# Sheet_1_2020-07-29_17-58-41.net
KiCad netlist of a schematic drawn in Altium Designer
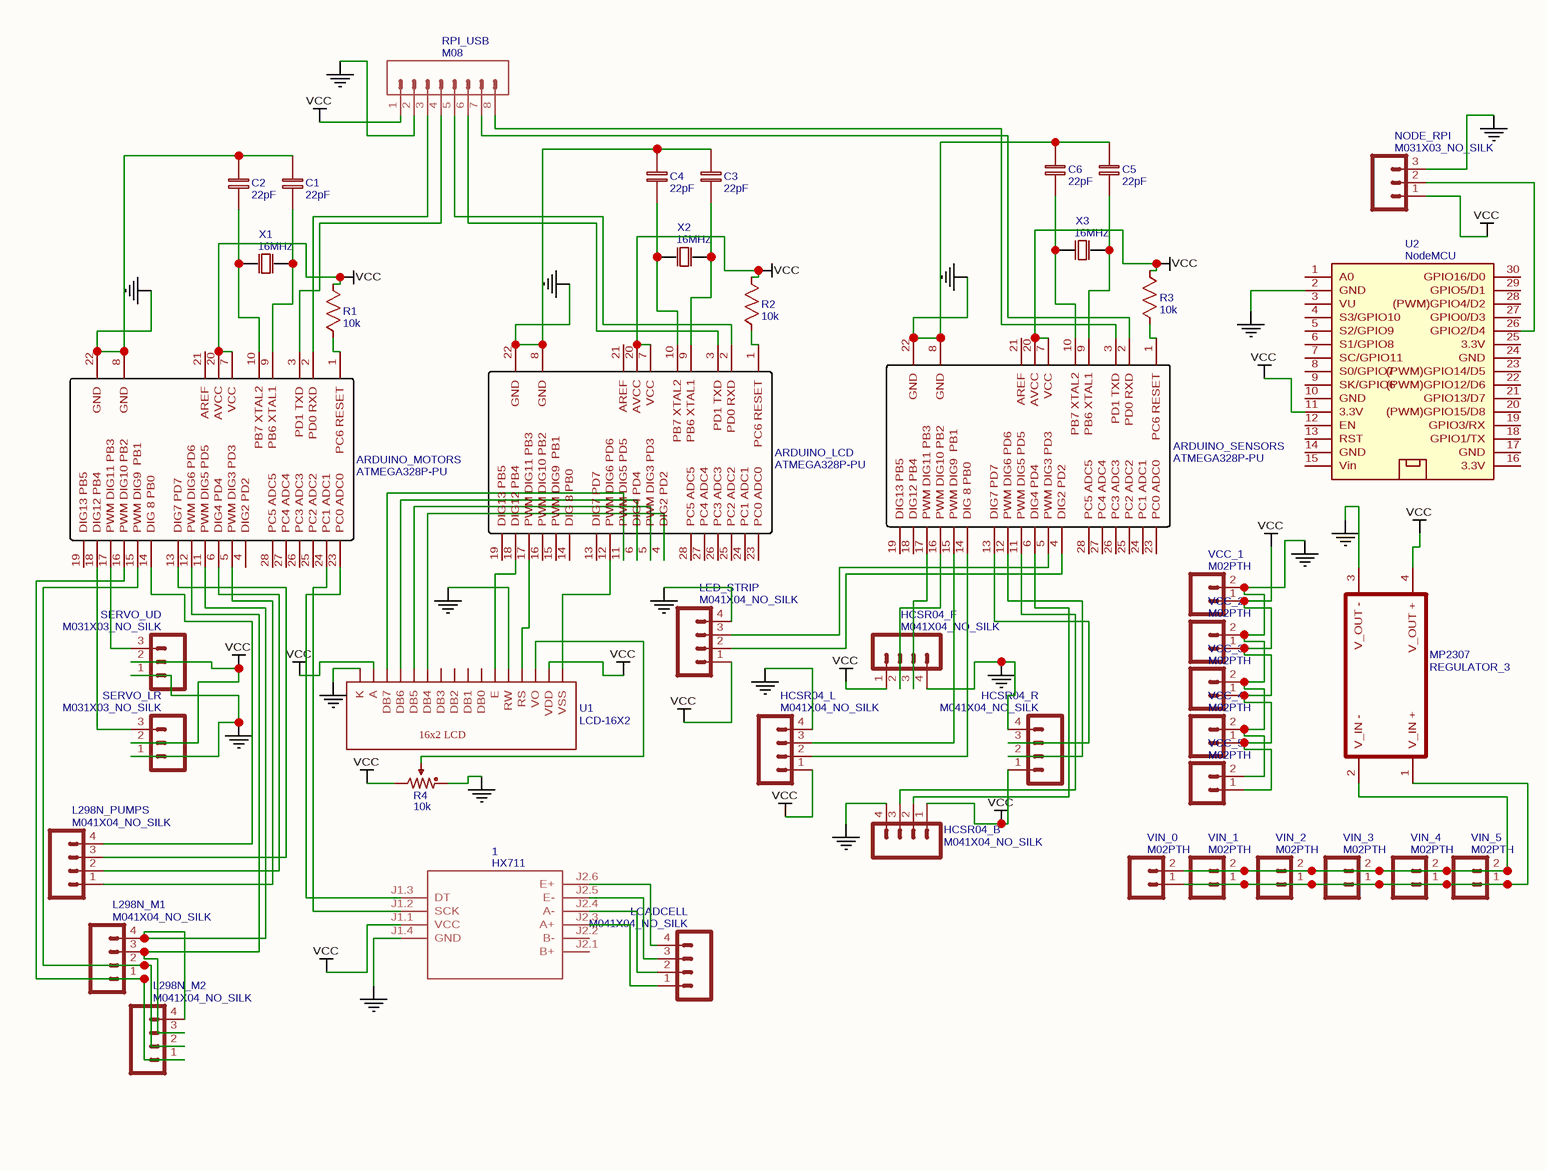
[diagram p0: Sheet_1_2020-07-29_17-58-41.schdoc, top left]
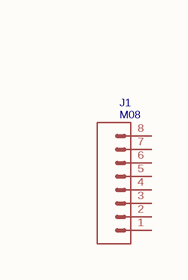
[diagram p1: Sheet_1_2020-07-29_17-58-41.schdoc, bottom right]

(export (version "E")
  (design (tool "Eeschema 10.0.6"))
  (components
    (comp (ref "1")
      (value "HX711")
      (fields (field (name "BOM_MANUFACTURER PART") "?") (field (name "CONTRIBUTOR") "Krzysztof Handzlik"))
      (libsource (lib "altium-import") (part "root_0_HX711_"))
    )
    (comp (ref "ARDUINO_LCD")
      (value "ATMEGA328P-PU")
      (fields (field (name "BOM_SUPPLIER PART") "C33901") (field (name "CONTRIBUTOR") "LCSC"))
      (libsource (lib "altium-import") (part "root_3_ATMEGA328P-PU_"))
    )
    (comp (ref "ARDUINO_MOTORS")
      (value "ATMEGA328P-PU")
      (fields (field (name "BOM_SUPPLIER PART") "C33901") (field (name "CONTRIBUTOR") "LCSC"))
      (libsource (lib "altium-import") (part "root_3_ATMEGA328P-PU_"))
    )
    (comp (ref "ARDUINO_SENSORS")
      (value "ATMEGA328P-PU")
      (fields (field (name "BOM_SUPPLIER PART") "C33901") (field (name "CONTRIBUTOR") "LCSC"))
      (libsource (lib "altium-import") (part "root_3_ATMEGA328P-PU_"))
    )
    (comp (ref "C1")
      (value "22pF")
      (fields (field (name "BOM_MANUFACTURER PART") "?"))
      (libsource (lib "altium-import") (part "root_2_22pF_"))
    )
    (comp (ref "C2")
      (value "22pF")
      (fields (field (name "BOM_MANUFACTURER PART") "?"))
      (libsource (lib "altium-import") (part "root_2_22pF_"))
    )
    (comp (ref "C3")
      (value "22pF")
      (fields (field (name "BOM_MANUFACTURER PART") "?"))
      (libsource (lib "altium-import") (part "root_2_22pF_"))
    )
    (comp (ref "C4")
      (value "22pF")
      (fields (field (name "BOM_MANUFACTURER PART") "?"))
      (libsource (lib "altium-import") (part "root_2_22pF_"))
    )
    (comp (ref "C5")
      (value "22pF")
      (fields (field (name "BOM_MANUFACTURER PART") "?"))
      (libsource (lib "altium-import") (part "root_2_22pF_"))
    )
    (comp (ref "C6")
      (value "22pF")
      (fields (field (name "BOM_MANUFACTURER PART") "?"))
      (libsource (lib "altium-import") (part "root_2_22pF_"))
    )
    (comp (ref "HCSR04_B")
      (value "M041X04_NO_SILK")
      (description "Header 4")
      (fields (field (name "BOM_MANUFACTURER PART") "?"))
      (libsource (lib "altium-import") (part "root_1_M041X04_NO_SILK_"))
    )
    (comp (ref "HCSR04_F")
      (value "M041X04_NO_SILK")
      (description "Header 4")
      (fields (field (name "BOM_MANUFACTURER PART") "?"))
      (libsource (lib "altium-import") (part "root_3_M041X04_NO_SILK_"))
    )
    (comp (ref "HCSR04_L")
      (value "M041X04_NO_SILK")
      (description "Header 4")
      (fields (field (name "BOM_MANUFACTURER PART") "?"))
      (libsource (lib "") (part "root_0_M041X04_NO_SILK__1"))
    )
    (comp (ref "HCSR04_R")
      (value "M041X04_NO_SILK")
      (description "Header 4")
      (fields (field (name "BOM_MANUFACTURER PART") "?"))
      (libsource (lib "altium-import") (part "root_0_M041X04_NO_SILK_"))
    )
    (comp (ref "J1")
      (value "M08")
      (fields (field (name "BOM_MANUFACTURER PART") "?") (field (name "CONTRIBUTOR") "Gilmar Junior"))
      (libsource (lib "altium-import") (part "root_0_M08_"))
    )
    (comp (ref "L298N_M1")
      (value "M041X04_NO_SILK")
      (description "Header 4")
      (fields (field (name "BOM_MANUFACTURER PART") "?"))
      (libsource (lib "") (part "root_0_M041X04_NO_SILK__1"))
    )
    (comp (ref "L298N_M2")
      (value "M041X04_NO_SILK")
      (description "Header 4")
      (fields (field (name "BOM_MANUFACTURER PART") "?"))
      (libsource (lib "") (part "root_0_M041X04_NO_SILK__1"))
    )
    (comp (ref "L298N_PUMPS")
      (value "M041X04_NO_SILK")
      (description "Header 4")
      (fields (field (name "BOM_MANUFACTURER PART") "?"))
      (libsource (lib "") (part "root_0_M041X04_NO_SILK__1"))
    )
    (comp (ref "LED_STRIP")
      (value "M041X04_NO_SILK")
      (description "Header 4")
      (fields (field (name "BOM_MANUFACTURER PART") "?"))
      (libsource (lib "") (part "root_0_M041X04_NO_SILK__1"))
    )
    (comp (ref "LOADCELL")
      (value "M041X04_NO_SILK")
      (description "Header 4")
      (fields (field (name "BOM_MANUFACTURER PART") "?"))
      (libsource (lib "altium-import") (part "root_0_M041X04_NO_SILK_"))
    )
    (comp (ref "NODE_RPI")
      (value "M031X03_NO_SILK")
      (description "Header 3")
      (fields (field (name "BOM_MANUFACTURER PART") "?"))
      (libsource (lib "") (part "root_0_M031X03_NO_SILK__1"))
    )
    (comp (ref "R1")
      (value "10k")
      (fields (field (name "BOM_MANUFACTURER PART") "?"))
      (libsource (lib "altium-import") (part "root_3_10k_"))
    )
    (comp (ref "R2")
      (value "10k")
      (fields (field (name "BOM_MANUFACTURER PART") "?"))
      (libsource (lib "altium-import") (part "root_3_10k_"))
    )
    (comp (ref "R3")
      (value "10k")
      (fields (field (name "BOM_MANUFACTURER PART") "?"))
      (libsource (lib "altium-import") (part "root_3_10k_"))
    )
    (comp (ref "R4")
      (value "10k")
      (fields
        (field (name "BOM_MANUFACTURER PART") "3386P-1-101LF")
        (field (name "BOM_SUPPLIER PART") "C125022")
        (field (name "CONTRIBUTOR") "EasyEDA")
      )
      (libsource (lib "altium-import") (part "root_0_10k_"))
    )
    (comp (ref "REGULATOR_3")
      (value "MP2307")
      (fields (field (name "BOM_MANUFACTURER PART") "?"))
      (libsource (lib "altium-import") (part "root_3_MP2307_"))
    )
    (comp (ref "RPI_USB")
      (value "M08")
      (fields (field (name "BOM_MANUFACTURER PART") "?") (field (name "CONTRIBUTOR") "Gilmar Junior"))
      (libsource (lib "altium-import") (part "root_3_M08_"))
    )
    (comp (ref "SERVO_LR")
      (value "M031X03_NO_SILK")
      (description "Header 3")
      (fields (field (name "BOM_MANUFACTURER PART") "?"))
      (libsource (lib "altium-import") (part "root_0_M031X03_NO_SILK_"))
    )
    (comp (ref "SERVO_UD")
      (value "M031X03_NO_SILK")
      (description "Header 3")
      (fields (field (name "BOM_MANUFACTURER PART") "?"))
      (libsource (lib "altium-import") (part "root_0_M031X03_NO_SILK_"))
    )
    (comp (ref "U1")
      (value "LCD-16X2")
      (fields (field (name "BOM_MANUFACTURER PART") "?") (field (name "CONTRIBUTOR") "SparkFun"))
      (libsource (lib "altium-import") (part "root_3_LCD-16X2_"))
    )
    (comp (ref "U2")
      (value "NodeMCU")
      (fields
        (field (name "BOM_MANUFACTURER PART") "NodeMcu V3 LoLin")
        (field (name "CONTRIBUTOR") "Rudiawan Edwin, M.Si, M.PKim")
      )
      (libsource (lib "altium-import") (part "root_0_NodeMCU_"))
    )
    (comp (ref "VCC_1")
      (value "M02PTH")
      (description "Header 2")
      (fields (field (name "BOM_MANUFACTURER PART") "?"))
      (libsource (lib "altium-import") (part "root_0_M02PTH_"))
    )
    (comp (ref "VCC_2")
      (value "M02PTH")
      (description "Header 2")
      (fields (field (name "BOM_MANUFACTURER PART") "?"))
      (libsource (lib "altium-import") (part "root_0_M02PTH_"))
    )
    (comp (ref "VCC_3")
      (value "M02PTH")
      (description "Header 2")
      (fields (field (name "BOM_MANUFACTURER PART") "?"))
      (libsource (lib "altium-import") (part "root_0_M02PTH_"))
    )
    (comp (ref "VCC_4")
      (value "M02PTH")
      (description "Header 2")
      (fields (field (name "BOM_MANUFACTURER PART") "?"))
      (libsource (lib "altium-import") (part "root_0_M02PTH_"))
    )
    (comp (ref "VCC_5")
      (value "M02PTH")
      (description "Header 2")
      (fields (field (name "BOM_MANUFACTURER PART") "?"))
      (libsource (lib "altium-import") (part "root_0_M02PTH_"))
    )
    (comp (ref "VIN_0")
      (value "M02PTH")
      (description "Header 2")
      (fields (field (name "BOM_MANUFACTURER PART") "?"))
      (libsource (lib "altium-import") (part "root_0_M02PTH_"))
    )
    (comp (ref "VIN_1")
      (value "M02PTH")
      (description "Header 2")
      (fields (field (name "BOM_MANUFACTURER PART") "?"))
      (libsource (lib "altium-import") (part "root_0_M02PTH_"))
    )
    (comp (ref "VIN_2")
      (value "M02PTH")
      (description "Header 2")
      (fields (field (name "BOM_MANUFACTURER PART") "?"))
      (libsource (lib "altium-import") (part "root_0_M02PTH_"))
    )
    (comp (ref "VIN_3")
      (value "M02PTH")
      (description "Header 2")
      (fields (field (name "BOM_MANUFACTURER PART") "?"))
      (libsource (lib "altium-import") (part "root_0_M02PTH_"))
    )
    (comp (ref "VIN_4")
      (value "M02PTH")
      (description "Header 2")
      (fields (field (name "BOM_MANUFACTURER PART") "?"))
      (libsource (lib "altium-import") (part "root_0_M02PTH_"))
    )
    (comp (ref "VIN_5")
      (value "M02PTH")
      (description "Header 2")
      (fields (field (name "BOM_MANUFACTURER PART") "?"))
      (libsource (lib "altium-import") (part "root_0_M02PTH_"))
    )
    (comp (ref "X1")
      (value "16MHz")
      (fields
        (field (name "BOM_MANUFACTURER PART") "X49SD12MSD2SC")
        (field (name "BOM_SUPPLIER PART") "C16369")
      )
      (libsource (lib "altium-import") (part "root_2_16MHz_"))
    )
    (comp (ref "X2")
      (value "16MHz")
      (fields
        (field (name "BOM_MANUFACTURER PART") "X49SD12MSD2SC")
        (field (name "BOM_SUPPLIER PART") "C16369")
      )
      (libsource (lib "altium-import") (part "root_2_16MHz_"))
    )
    (comp (ref "X3")
      (value "16MHz")
      (fields
        (field (name "BOM_MANUFACTURER PART") "X49SD12MSD2SC")
        (field (name "BOM_SUPPLIER PART") "C16369")
      )
      (libsource (lib "altium-import") (part "root_2_16MHz_"))
    )
  )
  (nets
    (net (code "1") (name "GND") (class "Default")
      (node (ref "1") (pin "J1.4") (pinfunction "GND_J1.4") (pintype "passive"))
      (node (ref "ARDUINO_LCD") (pin "22") (pinfunction "GND_22") (pintype "passive"))
      (node (ref "ARDUINO_LCD") (pin "8") (pinfunction "GND_8") (pintype "passive"))
      (node (ref "ARDUINO_MOTORS") (pin "22") (pinfunction "GND_22") (pintype "passive"))
      (node (ref "ARDUINO_MOTORS") (pin "8") (pinfunction "GND_8") (pintype "passive"))
      (node (ref "ARDUINO_SENSORS") (pin "22") (pinfunction "GND_22") (pintype "passive"))
      (node (ref "ARDUINO_SENSORS") (pin "8") (pinfunction "GND_8") (pintype "passive"))
      (node (ref "C1") (pin "2") (pinfunction "2_2") (pintype "passive"))
      (node (ref "C2") (pin "2") (pinfunction "2_2") (pintype "passive"))
      (node (ref "C3") (pin "2") (pinfunction "2_2") (pintype "passive"))
      (node (ref "C4") (pin "2") (pinfunction "2_2") (pintype "passive"))
      (node (ref "C5") (pin "2") (pinfunction "2_2") (pintype "passive"))
      (node (ref "C6") (pin "2") (pinfunction "2_2") (pintype "passive"))
      (node (ref "HCSR04_B") (pin "4") (pinfunction "4_4") (pintype "passive"))
      (node (ref "HCSR04_F") (pin "4") (pinfunction "4_4") (pintype "passive"))
      (node (ref "HCSR04_L") (pin "4") (pinfunction "4_4") (pintype "passive"))
      (node (ref "HCSR04_R") (pin "4") (pinfunction "4_4") (pintype "passive"))
      (node (ref "LED_STRIP") (pin "4") (pinfunction "4_4") (pintype "passive"))
      (node (ref "NODE_RPI") (pin "3") (pinfunction "3_3") (pintype "passive"))
      (node (ref "R4") (pin "1") (pinfunction "1_1") (pintype "passive"))
      (node (ref "REGULATOR_3") (pin "3") (pinfunction "V_OUT_-_3") (pintype "passive"))
      (node (ref "RPI_USB") (pin "2") (pinfunction "2_2") (pintype "passive"))
      (node (ref "SERVO_LR") (pin "1") (pinfunction "1_1") (pintype "passive"))
      (node (ref "SERVO_UD") (pin "1") (pinfunction "1_1") (pintype "passive"))
      (node (ref "U1") (pin "16") (pinfunction "K_16") (pintype "passive"))
      (node (ref "U1") (pin "5") (pinfunction "RW_5") (pintype "passive"))
      (node (ref "U2") (pin "2") (pinfunction "GND_2") (pintype "passive"))
      (node (ref "VCC_1") (pin "2") (pinfunction "2_2") (pintype "passive"))
      (node (ref "VCC_2") (pin "2") (pinfunction "2_2") (pintype "passive"))
      (node (ref "VCC_3") (pin "2") (pinfunction "2_2") (pintype "passive"))
      (node (ref "VCC_4") (pin "2") (pinfunction "2_2") (pintype "passive"))
      (node (ref "VCC_5") (pin "2") (pinfunction "2_2") (pintype "passive"))
    )
    (net (code "2") (name "Net-(1-A+)") (class "Default")
      (node (ref "1") (pin "J2.3") (pinfunction "A+_J2.3") (pintype "passive"))
      (node (ref "LOADCELL") (pin "1") (pinfunction "1_1") (pintype "passive"))
    )
    (net (code "3") (name "Net-(1-A-)") (class "Default")
      (node (ref "1") (pin "J2.4") (pinfunction "A-_J2.4") (pintype "passive"))
      (node (ref "LOADCELL") (pin "2") (pinfunction "2_2") (pintype "passive"))
    )
    (net (code "4") (name "Net-(1-DT)") (class "Default")
      (node (ref "1") (pin "J1.3") (pinfunction "DT_J1.3") (pintype "passive"))
      (node (ref "ARDUINO_MOTORS") (pin "23") (pinfunction "PC0_ADC0_23") (pintype "passive"))
    )
    (net (code "5") (name "Net-(1-E+)") (class "Default")
      (node (ref "1") (pin "J2.6") (pinfunction "E+_J2.6") (pintype "passive"))
      (node (ref "LOADCELL") (pin "4") (pinfunction "4_4") (pintype "passive"))
    )
    (net (code "6") (name "Net-(1-E-)") (class "Default")
      (node (ref "1") (pin "J2.5") (pinfunction "E-_J2.5") (pintype "passive"))
      (node (ref "LOADCELL") (pin "3") (pinfunction "3_3") (pintype "passive"))
    )
    (net (code "7") (name "Net-(1-SCK)") (class "Default")
      (node (ref "1") (pin "J1.2") (pinfunction "SCK_J1.2") (pintype "passive"))
      (node (ref "ARDUINO_MOTORS") (pin "24") (pinfunction "PC1_ADC1_24") (pintype "passive"))
    )
    (net (code "8") (name "Net-(ARDUINO_LCD-DIG2_PD2)") (class "Default")
      (node (ref "ARDUINO_LCD") (pin "4") (pinfunction "DIG2_PD2_4") (pintype "passive"))
      (node (ref "U1") (pin "11") (pinfunction "DB4_11") (pintype "passive"))
    )
    (net (code "9") (name "Net-(ARDUINO_LCD-DIG4_PD4)") (class "Default")
      (node (ref "ARDUINO_LCD") (pin "6") (pinfunction "DIG4_PD4_6") (pintype "passive"))
      (node (ref "U1") (pin "13") (pinfunction "DB6_13") (pintype "passive"))
    )
    (net (code "10") (name "Net-(ARDUINO_LCD-DIG12_PB4)") (class "Default")
      (node (ref "ARDUINO_LCD") (pin "18") (pinfunction "DIG12_PB4_18") (pintype "passive"))
      (node (ref "U1") (pin "6") (pinfunction "E_6") (pintype "passive"))
    )
    (net (code "11") (name "Net-(ARDUINO_LCD-PB6_XTAL1)") (class "Default")
      (node (ref "ARDUINO_LCD") (pin "9") (pinfunction "PB6_XTAL1_9") (pintype "passive"))
      (node (ref "C3") (pin "1") (pinfunction "1_1") (pintype "passive"))
      (node (ref "X2") (pin "2") (pinfunction "OSC2_2") (pintype "passive"))
    )
    (net (code "12") (name "Net-(ARDUINO_LCD-PB7_XTAL2)") (class "Default")
      (node (ref "ARDUINO_LCD") (pin "10") (pinfunction "PB7_XTAL2_10") (pintype "passive"))
      (node (ref "C4") (pin "1") (pinfunction "1_1") (pintype "passive"))
      (node (ref "X2") (pin "1") (pinfunction "OSC1_1") (pintype "passive"))
    )
    (net (code "13") (name "Net-(ARDUINO_LCD-PC6_RESET)") (class "Default")
      (node (ref "ARDUINO_LCD") (pin "1") (pinfunction "PC6_RESET_1") (pintype "passive"))
      (node (ref "R2") (pin "2") (pinfunction "2_2") (pintype "passive"))
    )
    (net (code "14") (name "Net-(ARDUINO_LCD-PD0_RXD)") (class "Default")
      (node (ref "ARDUINO_LCD") (pin "2") (pinfunction "PD0_RXD_2") (pintype "passive"))
      (node (ref "RPI_USB") (pin "5") (pinfunction "5_5") (pintype "passive"))
    )
    (net (code "15") (name "Net-(ARDUINO_LCD-PD1_TXD)") (class "Default")
      (node (ref "ARDUINO_LCD") (pin "3") (pinfunction "PD1_TXD_3") (pintype "passive"))
      (node (ref "RPI_USB") (pin "6") (pinfunction "6_6") (pintype "passive"))
    )
    (net (code "16") (name "Net-(ARDUINO_LCD-PWM_DIG3_PD3)") (class "Default")
      (node (ref "ARDUINO_LCD") (pin "5") (pinfunction "PWM_DIG3_PD3_5") (pintype "passive"))
      (node (ref "U1") (pin "12") (pinfunction "DB5_12") (pintype "passive"))
    )
    (net (code "17") (name "Net-(ARDUINO_LCD-PWM_DIG5_PD5)") (class "Default")
      (node (ref "ARDUINO_LCD") (pin "11") (pinfunction "PWM_DIG5_PD5_11") (pintype "passive"))
      (node (ref "U1") (pin "14") (pinfunction "DB7_14") (pintype "passive"))
    )
    (net (code "18") (name "Net-(ARDUINO_LCD-PWM_DIG6_PD6)") (class "Default")
      (node (ref "ARDUINO_LCD") (pin "12") (pinfunction "PWM_DIG6_PD6_12") (pintype "passive"))
      (node (ref "U1") (pin "1") (pinfunction "VSS_1") (pintype "passive"))
    )
    (net (code "19") (name "Net-(ARDUINO_LCD-PWM_DIG11_PB3)") (class "Default")
      (node (ref "ARDUINO_LCD") (pin "17") (pinfunction "PWM_DIG11_PB3_17") (pintype "passive"))
      (node (ref "U1") (pin "4") (pinfunction "RS_4") (pintype "passive"))
    )
    (net (code "20") (name "Net-(ARDUINO_MOTORS-DIG4_PD4)") (class "Default")
      (node (ref "ARDUINO_MOTORS") (pin "6") (pinfunction "DIG4_PD4_6") (pintype "passive"))
      (node (ref "L298N_PUMPS") (pin "2") (pinfunction "2_2") (pintype "passive"))
    )
    (net (code "21") (name "Net-(ARDUINO_MOTORS-DIG7_PD7)") (class "Default")
      (node (ref "ARDUINO_MOTORS") (pin "13") (pinfunction "DIG7_PD7_13") (pintype "passive"))
      (node (ref "L298N_PUMPS") (pin "3") (pinfunction "3_3") (pintype "passive"))
    )
    (net (code "22") (name "Net-(ARDUINO_MOTORS-DIG12_PB4)") (class "Default")
      (node (ref "ARDUINO_MOTORS") (pin "18") (pinfunction "DIG12_PB4_18") (pintype "passive"))
      (node (ref "SERVO_LR") (pin "3") (pinfunction "3_3") (pintype "passive"))
    )
    (net (code "23") (name "Net-(ARDUINO_MOTORS-DIG_8_PB0)") (class "Default")
      (node (ref "ARDUINO_MOTORS") (pin "14") (pinfunction "DIG_8_PB0_14") (pintype "passive"))
      (node (ref "L298N_PUMPS") (pin "4") (pinfunction "4_4") (pintype "passive"))
    )
    (net (code "24") (name "Net-(ARDUINO_MOTORS-PB6_XTAL1)") (class "Default")
      (node (ref "ARDUINO_MOTORS") (pin "9") (pinfunction "PB6_XTAL1_9") (pintype "passive"))
      (node (ref "C1") (pin "1") (pinfunction "1_1") (pintype "passive"))
      (node (ref "X1") (pin "2") (pinfunction "OSC2_2") (pintype "passive"))
    )
    (net (code "25") (name "Net-(ARDUINO_MOTORS-PB7_XTAL2)") (class "Default")
      (node (ref "ARDUINO_MOTORS") (pin "10") (pinfunction "PB7_XTAL2_10") (pintype "passive"))
      (node (ref "C2") (pin "1") (pinfunction "1_1") (pintype "passive"))
      (node (ref "X1") (pin "1") (pinfunction "OSC1_1") (pintype "passive"))
    )
    (net (code "26") (name "Net-(ARDUINO_MOTORS-PC6_RESET)") (class "Default")
      (node (ref "ARDUINO_MOTORS") (pin "1") (pinfunction "PC6_RESET_1") (pintype "passive"))
      (node (ref "R1") (pin "2") (pinfunction "2_2") (pintype "passive"))
    )
    (net (code "27") (name "Net-(ARDUINO_MOTORS-PD0_RXD)") (class "Default")
      (node (ref "ARDUINO_MOTORS") (pin "2") (pinfunction "PD0_RXD_2") (pintype "passive"))
      (node (ref "RPI_USB") (pin "3") (pinfunction "3_3") (pintype "passive"))
    )
    (net (code "28") (name "Net-(ARDUINO_MOTORS-PD1_TXD)") (class "Default")
      (node (ref "ARDUINO_MOTORS") (pin "3") (pinfunction "PD1_TXD_3") (pintype "passive"))
      (node (ref "RPI_USB") (pin "4") (pinfunction "4_4") (pintype "passive"))
    )
    (net (code "29") (name "Net-(ARDUINO_MOTORS-PWM_DIG3_PD3)") (class "Default")
      (node (ref "ARDUINO_MOTORS") (pin "5") (pinfunction "PWM_DIG3_PD3_5") (pintype "passive"))
      (node (ref "L298N_PUMPS") (pin "1") (pinfunction "1_1") (pintype "passive"))
    )
    (net (code "30") (name "Net-(ARDUINO_MOTORS-PWM_DIG5_PD5)") (class "Default")
      (node (ref "ARDUINO_MOTORS") (pin "11") (pinfunction "PWM_DIG5_PD5_11") (pintype "passive"))
      (node (ref "L298N_M1") (pin "4") (pinfunction "4_4") (pintype "passive"))
      (node (ref "L298N_M2") (pin "4") (pinfunction "4_4") (pintype "passive"))
    )
    (net (code "31") (name "Net-(ARDUINO_MOTORS-PWM_DIG6_PD6)") (class "Default")
      (node (ref "ARDUINO_MOTORS") (pin "12") (pinfunction "PWM_DIG6_PD6_12") (pintype "passive"))
      (node (ref "L298N_M1") (pin "3") (pinfunction "3_3") (pintype "passive"))
      (node (ref "L298N_M2") (pin "3") (pinfunction "3_3") (pintype "passive"))
    )
    (net (code "32") (name "Net-(ARDUINO_MOTORS-PWM_DIG9__PB1)") (class "Default")
      (node (ref "ARDUINO_MOTORS") (pin "15") (pinfunction "PWM_DIG9__PB1_15") (pintype "passive"))
      (node (ref "L298N_M1") (pin "2") (pinfunction "2_2") (pintype "passive"))
      (node (ref "L298N_M2") (pin "2") (pinfunction "2_2") (pintype "passive"))
    )
    (net (code "33") (name "Net-(ARDUINO_MOTORS-PWM_DIG10_PB2)") (class "Default")
      (node (ref "ARDUINO_MOTORS") (pin "16") (pinfunction "PWM_DIG10_PB2_16") (pintype "passive"))
      (node (ref "L298N_M1") (pin "1") (pinfunction "1_1") (pintype "passive"))
      (node (ref "L298N_M2") (pin "1") (pinfunction "1_1") (pintype "passive"))
    )
    (net (code "34") (name "Net-(ARDUINO_MOTORS-PWM_DIG11_PB3)") (class "Default")
      (node (ref "ARDUINO_MOTORS") (pin "17") (pinfunction "PWM_DIG11_PB3_17") (pintype "passive"))
      (node (ref "SERVO_UD") (pin "3") (pinfunction "3_3") (pintype "passive"))
    )
    (net (code "35") (name "Net-(ARDUINO_SENSORS-DIG2_PD2)") (class "Default")
      (node (ref "ARDUINO_SENSORS") (pin "4") (pinfunction "DIG2_PD2_4") (pintype "passive"))
      (node (ref "LED_STRIP") (pin "2") (pinfunction "2_2") (pintype "passive"))
    )
    (net (code "36") (name "Net-(ARDUINO_SENSORS-DIG4_PD4)") (class "Default")
      (node (ref "ARDUINO_SENSORS") (pin "6") (pinfunction "DIG4_PD4_6") (pintype "passive"))
      (node (ref "HCSR04_B") (pin "2") (pinfunction "2_2") (pintype "passive"))
    )
    (net (code "37") (name "Net-(ARDUINO_SENSORS-DIG7_PD7)") (class "Default")
      (node (ref "ARDUINO_SENSORS") (pin "13") (pinfunction "DIG7_PD7_13") (pintype "passive"))
      (node (ref "HCSR04_R") (pin "3") (pinfunction "3_3") (pintype "passive"))
    )
    (net (code "38") (name "Net-(ARDUINO_SENSORS-DIG_8_PB0)") (class "Default")
      (node (ref "ARDUINO_SENSORS") (pin "14") (pinfunction "DIG_8_PB0_14") (pintype "passive"))
      (node (ref "HCSR04_L") (pin "2") (pinfunction "2_2") (pintype "passive"))
    )
    (net (code "39") (name "Net-(ARDUINO_SENSORS-PB6_XTAL1)") (class "Default")
      (node (ref "ARDUINO_SENSORS") (pin "9") (pinfunction "PB6_XTAL1_9") (pintype "passive"))
      (node (ref "C5") (pin "1") (pinfunction "1_1") (pintype "passive"))
      (node (ref "X3") (pin "2") (pinfunction "OSC2_2") (pintype "passive"))
    )
    (net (code "40") (name "Net-(ARDUINO_SENSORS-PB7_XTAL2)") (class "Default")
      (node (ref "ARDUINO_SENSORS") (pin "10") (pinfunction "PB7_XTAL2_10") (pintype "passive"))
      (node (ref "C6") (pin "1") (pinfunction "1_1") (pintype "passive"))
      (node (ref "X3") (pin "1") (pinfunction "OSC1_1") (pintype "passive"))
    )
    (net (code "41") (name "Net-(ARDUINO_SENSORS-PC6_RESET)") (class "Default")
      (node (ref "ARDUINO_SENSORS") (pin "1") (pinfunction "PC6_RESET_1") (pintype "passive"))
      (node (ref "R3") (pin "2") (pinfunction "2_2") (pintype "passive"))
    )
    (net (code "42") (name "Net-(ARDUINO_SENSORS-PD0_RXD)") (class "Default")
      (node (ref "ARDUINO_SENSORS") (pin "2") (pinfunction "PD0_RXD_2") (pintype "passive"))
      (node (ref "RPI_USB") (pin "7") (pinfunction "7_7") (pintype "passive"))
    )
    (net (code "43") (name "Net-(ARDUINO_SENSORS-PD1_TXD)") (class "Default")
      (node (ref "ARDUINO_SENSORS") (pin "3") (pinfunction "PD1_TXD_3") (pintype "passive"))
      (node (ref "RPI_USB") (pin "8") (pinfunction "8_8") (pintype "passive"))
    )
    (net (code "44") (name "Net-(ARDUINO_SENSORS-PWM_DIG3_PD3)") (class "Default")
      (node (ref "ARDUINO_SENSORS") (pin "5") (pinfunction "PWM_DIG3_PD3_5") (pintype "passive"))
      (node (ref "LED_STRIP") (pin "3") (pinfunction "3_3") (pintype "passive"))
    )
    (net (code "45") (name "Net-(ARDUINO_SENSORS-PWM_DIG5_PD5)") (class "Default")
      (node (ref "ARDUINO_SENSORS") (pin "11") (pinfunction "PWM_DIG5_PD5_11") (pintype "passive"))
      (node (ref "HCSR04_B") (pin "3") (pinfunction "3_3") (pintype "passive"))
    )
    (net (code "46") (name "Net-(ARDUINO_SENSORS-PWM_DIG6_PD6)") (class "Default")
      (node (ref "ARDUINO_SENSORS") (pin "12") (pinfunction "PWM_DIG6_PD6_12") (pintype "passive"))
      (node (ref "HCSR04_R") (pin "2") (pinfunction "2_2") (pintype "passive"))
    )
    (net (code "47") (name "Net-(ARDUINO_SENSORS-PWM_DIG9__PB1)") (class "Default")
      (node (ref "ARDUINO_SENSORS") (pin "15") (pinfunction "PWM_DIG9__PB1_15") (pintype "passive"))
      (node (ref "HCSR04_L") (pin "3") (pinfunction "3_3") (pintype "passive"))
    )
    (net (code "48") (name "Net-(ARDUINO_SENSORS-PWM_DIG10_PB2)") (class "Default")
      (node (ref "ARDUINO_SENSORS") (pin "16") (pinfunction "PWM_DIG10_PB2_16") (pintype "passive"))
      (node (ref "HCSR04_F") (pin "2") (pinfunction "2_2") (pintype "passive"))
    )
    (net (code "49") (name "Net-(ARDUINO_SENSORS-PWM_DIG11_PB3)") (class "Default")
      (node (ref "ARDUINO_SENSORS") (pin "17") (pinfunction "PWM_DIG11_PB3_17") (pintype "passive"))
      (node (ref "HCSR04_F") (pin "3") (pinfunction "3_3") (pintype "passive"))
    )
    (net (code "50") (name "Net-(REGULATOR_3-V_IN_+)") (class "Default")
      (node (ref "REGULATOR_3") (pin "1") (pinfunction "V_IN_+_1") (pintype "passive"))
      (node (ref "VIN_0") (pin "1") (pinfunction "1_1") (pintype "passive"))
      (node (ref "VIN_1") (pin "1") (pinfunction "1_1") (pintype "passive"))
      (node (ref "VIN_2") (pin "1") (pinfunction "1_1") (pintype "passive"))
      (node (ref "VIN_3") (pin "1") (pinfunction "1_1") (pintype "passive"))
      (node (ref "VIN_4") (pin "1") (pinfunction "1_1") (pintype "passive"))
      (node (ref "VIN_5") (pin "1") (pinfunction "1_1") (pintype "passive"))
    )
    (net (code "51") (name "Net-(REGULATOR_3-V_IN_-)") (class "Default")
      (node (ref "REGULATOR_3") (pin "2") (pinfunction "V_IN_-_2") (pintype "passive"))
      (node (ref "VIN_0") (pin "2") (pinfunction "2_2") (pintype "passive"))
      (node (ref "VIN_1") (pin "2") (pinfunction "2_2") (pintype "passive"))
      (node (ref "VIN_2") (pin "2") (pinfunction "2_2") (pintype "passive"))
      (node (ref "VIN_3") (pin "2") (pinfunction "2_2") (pintype "passive"))
      (node (ref "VIN_4") (pin "2") (pinfunction "2_2") (pintype "passive"))
      (node (ref "VIN_5") (pin "2") (pinfunction "2_2") (pintype "passive"))
    )
    (net (code "52") (name "Net-(U1-VO)") (class "Default")
      (node (ref "R4") (pin "2") (pinfunction "2_2") (pintype "passive"))
      (node (ref "U1") (pin "3") (pinfunction "VO_3") (pintype "passive"))
    )
    (net (code "53") (name "Net-(U2-GPIO2{slash}D4)") (class "Default")
      (node (ref "NODE_RPI") (pin "2") (pinfunction "2_2") (pintype "passive"))
      (node (ref "U2") (pin "26") (pinfunction "GPIO2/D4_26") (pintype "passive"))
    )
    (net (code "54") (name "VCC") (class "Default")
      (node (ref "1") (pin "J1.1") (pinfunction "VCC_J1.1") (pintype "passive"))
      (node (ref "ARDUINO_LCD") (pin "20") (pinfunction "AVCC_20") (pintype "passive"))
      (node (ref "ARDUINO_LCD") (pin "7") (pinfunction "VCC_7") (pintype "passive"))
      (node (ref "ARDUINO_MOTORS") (pin "20") (pinfunction "AVCC_20") (pintype "passive"))
      (node (ref "ARDUINO_MOTORS") (pin "7") (pinfunction "VCC_7") (pintype "passive"))
      (node (ref "ARDUINO_SENSORS") (pin "20") (pinfunction "AVCC_20") (pintype "passive"))
      (node (ref "ARDUINO_SENSORS") (pin "7") (pinfunction "VCC_7") (pintype "passive"))
      (node (ref "HCSR04_B") (pin "1") (pinfunction "1_1") (pintype "passive"))
      (node (ref "HCSR04_F") (pin "1") (pinfunction "1_1") (pintype "passive"))
      (node (ref "HCSR04_L") (pin "1") (pinfunction "1_1") (pintype "passive"))
      (node (ref "HCSR04_R") (pin "1") (pinfunction "1_1") (pintype "passive"))
      (node (ref "LED_STRIP") (pin "1") (pinfunction "1_1") (pintype "passive"))
      (node (ref "NODE_RPI") (pin "1") (pinfunction "1_1") (pintype "passive"))
      (node (ref "R1") (pin "1") (pinfunction "1_1") (pintype "passive"))
      (node (ref "R2") (pin "1") (pinfunction "1_1") (pintype "passive"))
      (node (ref "R3") (pin "1") (pinfunction "1_1") (pintype "passive"))
      (node (ref "R4") (pin "3") (pinfunction "3_3") (pintype "passive"))
      (node (ref "REGULATOR_3") (pin "4") (pinfunction "V_OUT_+_4") (pintype "passive"))
      (node (ref "RPI_USB") (pin "1") (pinfunction "1_1") (pintype "passive"))
      (node (ref "SERVO_LR") (pin "2") (pinfunction "2_2") (pintype "passive"))
      (node (ref "SERVO_UD") (pin "2") (pinfunction "2_2") (pintype "passive"))
      (node (ref "U1") (pin "15") (pinfunction "A_15") (pintype "passive"))
      (node (ref "U1") (pin "2") (pinfunction "VDD_2") (pintype "passive"))
      (node (ref "U2") (pin "11") (pinfunction "3.3V_11") (pintype "passive"))
      (node (ref "VCC_1") (pin "1") (pinfunction "1_1") (pintype "passive"))
      (node (ref "VCC_2") (pin "1") (pinfunction "1_1") (pintype "passive"))
      (node (ref "VCC_3") (pin "1") (pinfunction "1_1") (pintype "passive"))
      (node (ref "VCC_4") (pin "1") (pinfunction "1_1") (pintype "passive"))
      (node (ref "VCC_5") (pin "1") (pinfunction "1_1") (pintype "passive"))
    )
    (net (code "55") (name "unconnected-(1-B+-PadJ2.1)") (class "Default")
      (node (ref "1") (pin "J2.1") (pinfunction "B+_J2.1") (pintype "passive"))
    )
    (net (code "56") (name "unconnected-(1-B--PadJ2.2)") (class "Default")
      (node (ref "1") (pin "J2.2") (pinfunction "B-_J2.2") (pintype "passive"))
    )
    (net (code "57") (name "unconnected-(ARDUINO_LCD-AREF-Pad21)") (class "Default")
      (node (ref "ARDUINO_LCD") (pin "21") (pinfunction "AREF_21") (pintype "passive"))
    )
    (net (code "58") (name "unconnected-(ARDUINO_LCD-DIG7_PD7-Pad13)") (class "Default")
      (node (ref "ARDUINO_LCD") (pin "13") (pinfunction "DIG7_PD7_13") (pintype "passive"))
    )
    (net (code "59") (name "unconnected-(ARDUINO_LCD-DIG13_PB5-Pad19)") (class "Default")
      (node (ref "ARDUINO_LCD") (pin "19") (pinfunction "DIG13_PB5_19") (pintype "passive"))
    )
    (net (code "60") (name "unconnected-(ARDUINO_LCD-DIG_8_PB0-Pad14)") (class "Default")
      (node (ref "ARDUINO_LCD") (pin "14") (pinfunction "DIG_8_PB0_14") (pintype "passive"))
    )
    (net (code "61") (name "unconnected-(ARDUINO_LCD-PC0_ADC0-Pad23)") (class "Default")
      (node (ref "ARDUINO_LCD") (pin "23") (pinfunction "PC0_ADC0_23") (pintype "passive"))
    )
    (net (code "62") (name "unconnected-(ARDUINO_LCD-PC1_ADC1-Pad24)") (class "Default")
      (node (ref "ARDUINO_LCD") (pin "24") (pinfunction "PC1_ADC1_24") (pintype "passive"))
    )
    (net (code "63") (name "unconnected-(ARDUINO_LCD-PC2_ADC2-Pad25)") (class "Default")
      (node (ref "ARDUINO_LCD") (pin "25") (pinfunction "PC2_ADC2_25") (pintype "passive"))
    )
    (net (code "64") (name "unconnected-(ARDUINO_LCD-PC3_ADC3-Pad26)") (class "Default")
      (node (ref "ARDUINO_LCD") (pin "26") (pinfunction "PC3_ADC3_26") (pintype "passive"))
    )
    (net (code "65") (name "unconnected-(ARDUINO_LCD-PC4_ADC4-Pad27)") (class "Default")
      (node (ref "ARDUINO_LCD") (pin "27") (pinfunction "PC4_ADC4_27") (pintype "passive"))
    )
    (net (code "66") (name "unconnected-(ARDUINO_LCD-PC5_ADC5-Pad28)") (class "Default")
      (node (ref "ARDUINO_LCD") (pin "28") (pinfunction "PC5_ADC5_28") (pintype "passive"))
    )
    (net (code "67") (name "unconnected-(ARDUINO_LCD-PWM_DIG9__PB1-Pad15)") (class "Default")
      (node (ref "ARDUINO_LCD") (pin "15") (pinfunction "PWM_DIG9__PB1_15") (pintype "passive"))
    )
    (net (code "68") (name "unconnected-(ARDUINO_LCD-PWM_DIG10_PB2-Pad16)") (class "Default")
      (node (ref "ARDUINO_LCD") (pin "16") (pinfunction "PWM_DIG10_PB2_16") (pintype "passive"))
    )
    (net (code "69") (name "unconnected-(ARDUINO_MOTORS-AREF-Pad21)") (class "Default")
      (node (ref "ARDUINO_MOTORS") (pin "21") (pinfunction "AREF_21") (pintype "passive"))
    )
    (net (code "70") (name "unconnected-(ARDUINO_MOTORS-DIG2_PD2-Pad4)") (class "Default")
      (node (ref "ARDUINO_MOTORS") (pin "4") (pinfunction "DIG2_PD2_4") (pintype "passive"))
    )
    (net (code "71") (name "unconnected-(ARDUINO_MOTORS-DIG13_PB5-Pad19)") (class "Default")
      (node (ref "ARDUINO_MOTORS") (pin "19") (pinfunction "DIG13_PB5_19") (pintype "passive"))
    )
    (net (code "72") (name "unconnected-(ARDUINO_MOTORS-PC2_ADC2-Pad25)") (class "Default")
      (node (ref "ARDUINO_MOTORS") (pin "25") (pinfunction "PC2_ADC2_25") (pintype "passive"))
    )
    (net (code "73") (name "unconnected-(ARDUINO_MOTORS-PC3_ADC3-Pad26)") (class "Default")
      (node (ref "ARDUINO_MOTORS") (pin "26") (pinfunction "PC3_ADC3_26") (pintype "passive"))
    )
    (net (code "74") (name "unconnected-(ARDUINO_MOTORS-PC4_ADC4-Pad27)") (class "Default")
      (node (ref "ARDUINO_MOTORS") (pin "27") (pinfunction "PC4_ADC4_27") (pintype "passive"))
    )
    (net (code "75") (name "unconnected-(ARDUINO_MOTORS-PC5_ADC5-Pad28)") (class "Default")
      (node (ref "ARDUINO_MOTORS") (pin "28") (pinfunction "PC5_ADC5_28") (pintype "passive"))
    )
    (net (code "76") (name "unconnected-(ARDUINO_SENSORS-AREF-Pad21)") (class "Default")
      (node (ref "ARDUINO_SENSORS") (pin "21") (pinfunction "AREF_21") (pintype "passive"))
    )
    (net (code "77") (name "unconnected-(ARDUINO_SENSORS-DIG12_PB4-Pad18)") (class "Default")
      (node (ref "ARDUINO_SENSORS") (pin "18") (pinfunction "DIG12_PB4_18") (pintype "passive"))
    )
    (net (code "78") (name "unconnected-(ARDUINO_SENSORS-DIG13_PB5-Pad19)") (class "Default")
      (node (ref "ARDUINO_SENSORS") (pin "19") (pinfunction "DIG13_PB5_19") (pintype "passive"))
    )
    (net (code "79") (name "unconnected-(ARDUINO_SENSORS-PC0_ADC0-Pad23)") (class "Default")
      (node (ref "ARDUINO_SENSORS") (pin "23") (pinfunction "PC0_ADC0_23") (pintype "passive"))
    )
    (net (code "80") (name "unconnected-(ARDUINO_SENSORS-PC1_ADC1-Pad24)") (class "Default")
      (node (ref "ARDUINO_SENSORS") (pin "24") (pinfunction "PC1_ADC1_24") (pintype "passive"))
    )
    (net (code "81") (name "unconnected-(ARDUINO_SENSORS-PC2_ADC2-Pad25)") (class "Default")
      (node (ref "ARDUINO_SENSORS") (pin "25") (pinfunction "PC2_ADC2_25") (pintype "passive"))
    )
    (net (code "82") (name "unconnected-(ARDUINO_SENSORS-PC3_ADC3-Pad26)") (class "Default")
      (node (ref "ARDUINO_SENSORS") (pin "26") (pinfunction "PC3_ADC3_26") (pintype "passive"))
    )
    (net (code "83") (name "unconnected-(ARDUINO_SENSORS-PC4_ADC4-Pad27)") (class "Default")
      (node (ref "ARDUINO_SENSORS") (pin "27") (pinfunction "PC4_ADC4_27") (pintype "passive"))
    )
    (net (code "84") (name "unconnected-(ARDUINO_SENSORS-PC5_ADC5-Pad28)") (class "Default")
      (node (ref "ARDUINO_SENSORS") (pin "28") (pinfunction "PC5_ADC5_28") (pintype "passive"))
    )
    (net (code "85") (name "unconnected-(J1-Pad1)") (class "Default")
      (node (ref "J1") (pin "1") (pinfunction "1_1") (pintype "passive"))
    )
    (net (code "86") (name "unconnected-(J1-Pad2)") (class "Default")
      (node (ref "J1") (pin "2") (pinfunction "2_2") (pintype "passive"))
    )
    (net (code "87") (name "unconnected-(J1-Pad3)") (class "Default")
      (node (ref "J1") (pin "3") (pinfunction "3_3") (pintype "passive"))
    )
    (net (code "88") (name "unconnected-(J1-Pad4)") (class "Default")
      (node (ref "J1") (pin "4") (pinfunction "4_4") (pintype "passive"))
    )
    (net (code "89") (name "unconnected-(J1-Pad5)") (class "Default")
      (node (ref "J1") (pin "5") (pinfunction "5_5") (pintype "passive"))
    )
    (net (code "90") (name "unconnected-(J1-Pad6)") (class "Default")
      (node (ref "J1") (pin "6") (pinfunction "6_6") (pintype "passive"))
    )
    (net (code "91") (name "unconnected-(J1-Pad7)") (class "Default")
      (node (ref "J1") (pin "7") (pinfunction "7_7") (pintype "passive"))
    )
    (net (code "92") (name "unconnected-(J1-Pad8)") (class "Default")
      (node (ref "J1") (pin "8") (pinfunction "8_8") (pintype "passive"))
    )
    (net (code "93") (name "unconnected-(U1-DB0-Pad7)") (class "Default")
      (node (ref "U1") (pin "7") (pinfunction "DB0_7") (pintype "passive"))
    )
    (net (code "94") (name "unconnected-(U1-DB1-Pad8)") (class "Default")
      (node (ref "U1") (pin "8") (pinfunction "DB1_8") (pintype "passive"))
    )
    (net (code "95") (name "unconnected-(U1-DB2-Pad9)") (class "Default")
      (node (ref "U1") (pin "9") (pinfunction "DB2_9") (pintype "passive"))
    )
    (net (code "96") (name "unconnected-(U1-DB3-Pad10)") (class "Default")
      (node (ref "U1") (pin "10") (pinfunction "DB3_10") (pintype "passive"))
    )
    (net (code "97") (name "unconnected-(U2-(PWM)GPIO4{slash}D2-Pad28)") (class "Default")
      (node (ref "U2") (pin "28") (pinfunction "(PWM)GPIO4/D2_28") (pintype "passive"))
    )
    (net (code "98") (name "unconnected-(U2-(PWM)GPIO12{slash}D6-Pad22)") (class "Default")
      (node (ref "U2") (pin "22") (pinfunction "(PWM)GPIO12/D6_22") (pintype "passive"))
    )
    (net (code "99") (name "unconnected-(U2-(PWM)GPIO14{slash}D5-Pad23)") (class "Default")
      (node (ref "U2") (pin "23") (pinfunction "(PWM)GPIO14/D5_23") (pintype "passive"))
    )
    (net (code "100") (name "unconnected-(U2-(PWM)GPIO15{slash}D8-Pad20)") (class "Default")
      (node (ref "U2") (pin "20") (pinfunction "(PWM)GPIO15/D8_20") (pintype "passive"))
    )
    (net (code "101") (name "unconnected-(U2-3.3V-Pad16)") (class "Default")
      (node (ref "U2") (pin "16") (pinfunction "3.3V_16") (pintype "passive"))
    )
    (net (code "102") (name "unconnected-(U2-3.3V-Pad25)") (class "Default")
      (node (ref "U2") (pin "25") (pinfunction "3.3V_25") (pintype "passive"))
    )
    (net (code "103") (name "unconnected-(U2-A0-Pad1)") (class "Default")
      (node (ref "U2") (pin "1") (pinfunction "A0_1") (pintype "passive"))
    )
    (net (code "104") (name "unconnected-(U2-EN-Pad12)") (class "Default")
      (node (ref "U2") (pin "12") (pinfunction "EN_12") (pintype "passive"))
    )
    (net (code "105") (name "unconnected-(U2-GND-Pad10)") (class "Default")
      (node (ref "U2") (pin "10") (pinfunction "GND_10") (pintype "passive"))
    )
    (net (code "106") (name "unconnected-(U2-GND-Pad14)") (class "Default")
      (node (ref "U2") (pin "14") (pinfunction "GND_14") (pintype "passive"))
    )
    (net (code "107") (name "unconnected-(U2-GND-Pad17)") (class "Default")
      (node (ref "U2") (pin "17") (pinfunction "GND_17") (pintype "passive"))
    )
    (net (code "108") (name "unconnected-(U2-GND-Pad24)") (class "Default")
      (node (ref "U2") (pin "24") (pinfunction "GND_24") (pintype "passive"))
    )
    (net (code "109") (name "unconnected-(U2-GPIO0{slash}D3-Pad27)") (class "Default")
      (node (ref "U2") (pin "27") (pinfunction "GPIO0/D3_27") (pintype "passive"))
    )
    (net (code "110") (name "unconnected-(U2-GPIO1{slash}TX-Pad18)") (class "Default")
      (node (ref "U2") (pin "18") (pinfunction "GPIO1/TX_18") (pintype "passive"))
    )
    (net (code "111") (name "unconnected-(U2-GPIO3{slash}RX-Pad19)") (class "Default")
      (node (ref "U2") (pin "19") (pinfunction "GPIO3/RX_19") (pintype "passive"))
    )
    (net (code "112") (name "unconnected-(U2-GPIO5{slash}D1-Pad29)") (class "Default")
      (node (ref "U2") (pin "29") (pinfunction "GPIO5/D1_29") (pintype "passive"))
    )
    (net (code "113") (name "unconnected-(U2-GPIO13{slash}D7-Pad21)") (class "Default")
      (node (ref "U2") (pin "21") (pinfunction "GPIO13/D7_21") (pintype "passive"))
    )
    (net (code "114") (name "unconnected-(U2-GPIO16{slash}D0-Pad30)") (class "Default")
      (node (ref "U2") (pin "30") (pinfunction "GPIO16/D0_30") (pintype "passive"))
    )
    (net (code "115") (name "unconnected-(U2-RST-Pad13)") (class "Default")
      (node (ref "U2") (pin "13") (pinfunction "RST_13") (pintype "passive"))
    )
    (net (code "116") (name "unconnected-(U2-S0{slash}GPIO7-Pad8)") (class "Default")
      (node (ref "U2") (pin "8") (pinfunction "S0/GPIO7_8") (pintype "passive"))
    )
    (net (code "117") (name "unconnected-(U2-S1{slash}GPIO8-Pad6)") (class "Default")
      (node (ref "U2") (pin "6") (pinfunction "S1/GPIO8_6") (pintype "passive"))
    )
    (net (code "118") (name "unconnected-(U2-S2{slash}GPIO9-Pad5)") (class "Default")
      (node (ref "U2") (pin "5") (pinfunction "S2/GPIO9_5") (pintype "passive"))
    )
    (net (code "119") (name "unconnected-(U2-S3{slash}GPIO10-Pad4)") (class "Default")
      (node (ref "U2") (pin "4") (pinfunction "S3/GPIO10_4") (pintype "passive"))
    )
    (net (code "120") (name "unconnected-(U2-SC{slash}GPIO11-Pad7)") (class "Default")
      (node (ref "U2") (pin "7") (pinfunction "SC/GPIO11_7") (pintype "passive"))
    )
    (net (code "121") (name "unconnected-(U2-SK{slash}GPIO6-Pad9)") (class "Default")
      (node (ref "U2") (pin "9") (pinfunction "SK/GPIO6_9") (pintype "passive"))
    )
    (net (code "122") (name "unconnected-(U2-VU-Pad3)") (class "Default")
      (node (ref "U2") (pin "3") (pinfunction "VU_3") (pintype "passive"))
    )
    (net (code "123") (name "unconnected-(U2-Vin-Pad15)") (class "Default")
      (node (ref "U2") (pin "15") (pinfunction "Vin_15") (pintype "passive"))
    )
  )
)
